# Load_Tester.net
KiCad netlist of a schematic drawn in Altium Designer
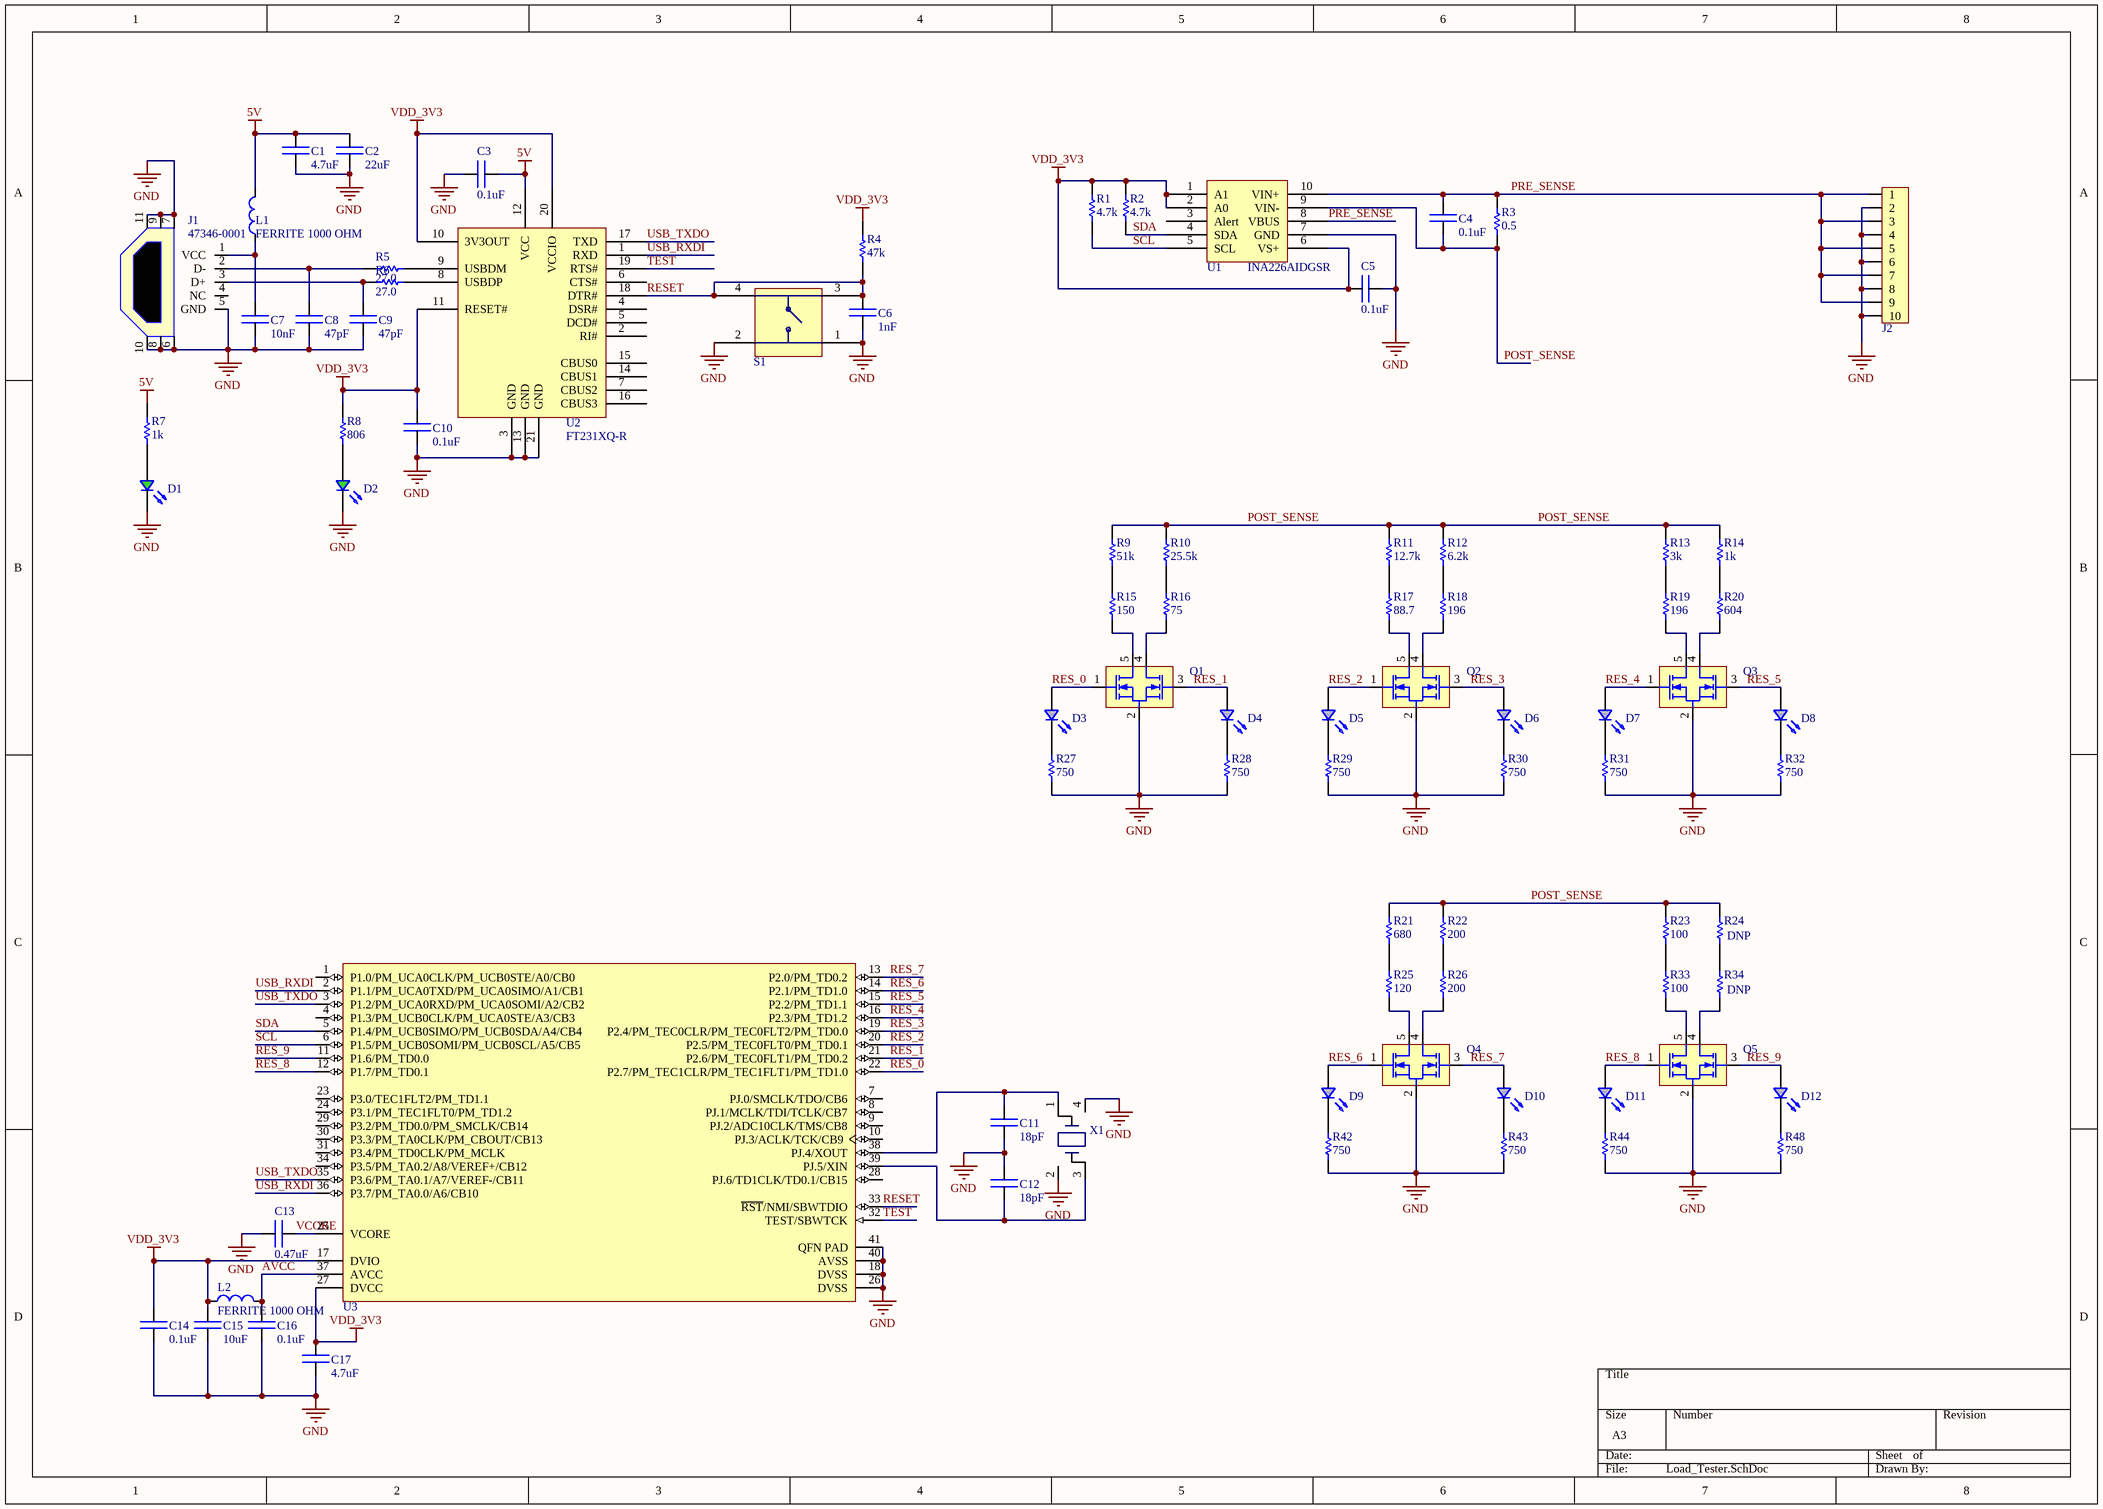
[diagram p0: Load_Tester.SchDoc]

(export (version "E")
  (design (tool "Eeschema 10.0.6"))
  (components
    (comp (ref "C1")
      (value "4.7uF")
      (footprint "0603_Cap_Generic")
      (description "CAP CER 4.7UF 35V X5R 0603")
      (fields
        (field (name "MC10 PART NUMBER") "100-00191")
        (field (name "MANUFACTURER") "TDK")
        (field (name "DRAWN BY") "EH")
      )
      (libsource (lib "MC10_Component_dblib_v1_0b2") (part "CAP CER 4.7UF 35V X5R 0603"))
    )
    (comp (ref "C2")
      (value "22uF")
      (footprint "0603_Cap_Generic")
      (description "CAP CER 22UF 10V X5R 0603")
      (fields
        (field (name "MC10 PART NUMBER") "100-00205")
        (field (name "MANUFACTURER") "TDK")
        (field (name "DRAWN BY") "EH")
      )
      (libsource (lib "MC10_Component_dblib_v1_0b2") (part "CAP CER 22UF 10V X5R 0603"))
    )
    (comp (ref "C3")
      (value "0.1uF")
      (footprint "0402_CAP_Generic")
      (description "CAP CER 0.1UF 25V X7R 0402")
      (fields
        (field (name "MC10 PART NUMBER") "100-00212")
        (field (name "MANUFACTURER") "TDK")
        (field (name "DRAWN BY") "EH")
      )
      (libsource (lib "MC10_Component_dblib_v1_0b2") (part "CAP CER 0.1UF 25V X7R 0402"))
    )
    (comp (ref "C4")
      (value "0.1uF")
      (footprint "0603_Cap_Generic")
      (description "CAP CER 0.1UF 25V X7R 0603")
      (fields
        (field (name "MC10 PART NUMBER") "100-00193")
        (field (name "MANUFACTURER") "TDK")
        (field (name "DRAWN BY") "EH")
      )
      (libsource (lib "MC10_Component_dblib_v1_0b2") (part "CAP CER 0.1UF 25V X7R 0603"))
    )
    (comp (ref "C5")
      (value "0.1uF")
      (footprint "0402_CAP_Generic")
      (description "CAP CER 0.1UF 25V X7R 0402")
      (fields
        (field (name "MC10 PART NUMBER") "100-00212")
        (field (name "MANUFACTURER") "TDK")
        (field (name "DRAWN BY") "EH")
      )
      (libsource (lib "MC10_Component_dblib_v1_0b2") (part "CAP CER 0.1UF 25V X7R 0402"))
    )
    (comp (ref "C6")
      (value "1nF")
      (footprint "0603_Cap_Generic")
      (description "CAP CER 1000PF 50V X7R 0603")
      (fields
        (field (name "MC10 PART NUMBER") "100-00211")
        (field (name "MANUFACTURER") "TDK")
        (field (name "DRAWN BY") "EH")
      )
      (libsource (lib "MC10_Component_dblib_v1_0b2") (part "CAP CER 1000PF 50V X7R 0603"))
    )
    (comp (ref "C7")
      (value "10nF")
      (footprint "0603_Cap_Generic")
      (description "CAP CER 10000PF 50V X7R 0603")
      (fields
        (field (name "MC10 PART NUMBER") "100-00189")
        (field (name "MANUFACTURER") "TDK")
        (field (name "DRAWN BY") "EH")
      )
      (libsource (lib "MC10_Component_dblib_v1_0b2") (part "CAP CER 10000PF 50V X7R 0603"))
    )
    (comp (ref "C8")
      (value "47pF")
      (footprint "0603_Cap_Generic")
      (description "CAP CER 47PF 50V C0G 0603")
      (fields
        (field (name "MC10 PART NUMBER") "100-00190")
        (field (name "MANUFACTURER") "TDK")
        (field (name "DRAWN BY") "EH")
      )
      (libsource (lib "MC10_Component_dblib_v1_0b2") (part "CAP CER 47PF 50V C0G 0603"))
    )
    (comp (ref "C9")
      (value "47pF")
      (footprint "0603_Cap_Generic")
      (description "CAP CER 47PF 50V C0G 0603")
      (fields
        (field (name "MC10 PART NUMBER") "100-00190")
        (field (name "MANUFACTURER") "TDK")
        (field (name "DRAWN BY") "EH")
      )
      (libsource (lib "MC10_Component_dblib_v1_0b2") (part "CAP CER 47PF 50V C0G 0603"))
    )
    (comp (ref "C10")
      (value "0.1uF")
      (footprint "0402_CAP_Generic")
      (description "CAP CER 0.1UF 25V X7R 0402")
      (fields
        (field (name "MC10 PART NUMBER") "100-00212")
        (field (name "MANUFACTURER") "TDK")
        (field (name "DRAWN BY") "EH")
      )
      (libsource (lib "MC10_Component_dblib_v1_0b2") (part "CAP CER 0.1UF 25V X7R 0402"))
    )
    (comp (ref "C11")
      (value "18pF")
      (footprint "0603_Cap_Generic")
      (description "CAP CER 18PF 50V C0G 0603")
      (fields
        (field (name "MC10 PART NUMBER") "100-00209")
        (field (name "MANUFACTURER") "TDK")
        (field (name "DRAWN BY") "EH")
      )
      (libsource (lib "MC10_Component_dblib_v1_0b2") (part "CAP CER 18PF 50V C0G 0603"))
    )
    (comp (ref "C12")
      (value "18pF")
      (footprint "0603_Cap_Generic")
      (description "CAP CER 18PF 50V C0G 0603")
      (fields
        (field (name "MC10 PART NUMBER") "100-00209")
        (field (name "MANUFACTURER") "TDK")
        (field (name "DRAWN BY") "EH")
      )
      (libsource (lib "MC10_Component_dblib_v1_0b2") (part "CAP CER 18PF 50V C0G 0603"))
    )
    (comp (ref "C13")
      (value "0.47uF")
      (footprint "0402_CAP_Generic")
      (description "CAP CER 0.47UF 10V X5R 0402")
      (fields
        (field (name "MC10 PART NUMBER") "100-00214")
        (field (name "MANUFACTURER") "TDK")
        (field (name "DRAWN BY") "EH")
      )
      (libsource (lib "MC10_Component_dblib_v1_0b2") (part "CAP CER 0.47UF 10V X5R 0402"))
    )
    (comp (ref "C14")
      (value "0.1uF")
      (footprint "0402_CAP_Generic")
      (description "CAP CER 0.1UF 25V X7R 0402")
      (fields
        (field (name "MC10 PART NUMBER") "100-00212")
        (field (name "MANUFACTURER") "TDK")
        (field (name "DRAWN BY") "EH")
      )
      (libsource (lib "MC10_Component_dblib_v1_0b2") (part "CAP CER 0.1UF 25V X7R 0402"))
    )
    (comp (ref "C15")
      (value "10uF")
      (footprint "0603_Cap_Generic")
      (description "CAP CER 10UF 10V JB 0603")
      (fields
        (field (name "MC10 PART NUMBER") "100-00208")
        (field (name "MANUFACTURER") "TDK")
        (field (name "DRAWN BY") "EH")
      )
      (libsource (lib "MC10_Component_dblib_v1_0b2") (part "CAP CER 10UF 10V JB 0603"))
    )
    (comp (ref "C16")
      (value "0.1uF")
      (footprint "0402_CAP_Generic")
      (description "CAP CER 0.1UF 25V X7R 0402")
      (fields
        (field (name "MC10 PART NUMBER") "100-00212")
        (field (name "MANUFACTURER") "TDK")
        (field (name "DRAWN BY") "EH")
      )
      (libsource (lib "MC10_Component_dblib_v1_0b2") (part "CAP CER 0.1UF 25V X7R 0402"))
    )
    (comp (ref "C17")
      (value "4.7uF")
      (footprint "0402_CAP_Generic")
      (description "CAP CER 4.7UF 10V X5R 0402")
      (fields
        (field (name "MC10 PART NUMBER") "100-00213")
        (field (name "MANUFACTURER") "TDK")
        (field (name "DRAWN BY") "EH")
      )
      (libsource (lib "MC10_Component_dblib_v1_0b2") (part "CAP CER 4.7UF 10V X5R 0402"))
    )
    (comp (ref "D1")
      (value "LED SMARTLED GREEN 570NM 0603")
      (footprint "0603_LED_with_mark")
      (fields
        (field (name "MANUFACTURER") "OSRAM Opto Semiconductors")
        (field (name "MANUFACTURER PART NUMBER") "LG L29K-G2J1-24-Z")
        (field (name "MC10 PART NUMBER") "200-00073")
        (field (name "DRAWN BY") "BLM")
      )
      (libsource (lib "MC10_Component_dblib_v1_0b2") (part "LED SMARTLED GREEN 570NM 0603"))
    )
    (comp (ref "D2")
      (value "LED SMARTLED GREEN 570NM 0603")
      (footprint "0603_LED_with_mark")
      (fields
        (field (name "MANUFACTURER") "OSRAM Opto Semiconductors")
        (field (name "MANUFACTURER PART NUMBER") "LG L29K-G2J1-24-Z")
        (field (name "MC10 PART NUMBER") "200-00073")
        (field (name "DRAWN BY") "BLM")
      )
      (libsource (lib "MC10_Component_dblib_v1_0b2") (part "LED SMARTLED GREEN 570NM 0603"))
    )
    (comp (ref "D3")
      (value "LED SMARTLED RED 630NM 0603 SMD")
      (footprint "0603_Diode-LED_Generic")
      (fields
        (field (name "MANUFACTURER") "OSRAM Opto Semiconductors")
        (field (name "MANUFACTURER PART NUMBER") "LS L29K-H1J2-1-Z")
        (field (name "MC10 PART NUMBER") "200-00031")
        (field (name "DRAWN BY") "BLM")
      )
      (libsource (lib "MC10_Component_dblib_v1_0b2") (part "LED SMARTLED RED 630NM 0603 SMD"))
    )
    (comp (ref "D4")
      (value "LED SMARTLED RED 630NM 0603 SMD")
      (footprint "0603_Diode-LED_Generic")
      (fields
        (field (name "MANUFACTURER") "OSRAM Opto Semiconductors")
        (field (name "MANUFACTURER PART NUMBER") "LS L29K-H1J2-1-Z")
        (field (name "MC10 PART NUMBER") "200-00031")
        (field (name "DRAWN BY") "BLM")
      )
      (libsource (lib "MC10_Component_dblib_v1_0b2") (part "LED SMARTLED RED 630NM 0603 SMD"))
    )
    (comp (ref "D5")
      (value "LED SMARTLED RED 630NM 0603 SMD")
      (footprint "0603_Diode-LED_Generic")
      (fields
        (field (name "MANUFACTURER") "OSRAM Opto Semiconductors")
        (field (name "MANUFACTURER PART NUMBER") "LS L29K-H1J2-1-Z")
        (field (name "MC10 PART NUMBER") "200-00031")
        (field (name "DRAWN BY") "BLM")
      )
      (libsource (lib "MC10_Component_dblib_v1_0b2") (part "LED SMARTLED RED 630NM 0603 SMD"))
    )
    (comp (ref "D6")
      (value "LED SMARTLED RED 630NM 0603 SMD")
      (footprint "0603_Diode-LED_Generic")
      (fields
        (field (name "MANUFACTURER") "OSRAM Opto Semiconductors")
        (field (name "MANUFACTURER PART NUMBER") "LS L29K-H1J2-1-Z")
        (field (name "MC10 PART NUMBER") "200-00031")
        (field (name "DRAWN BY") "BLM")
      )
      (libsource (lib "MC10_Component_dblib_v1_0b2") (part "LED SMARTLED RED 630NM 0603 SMD"))
    )
    (comp (ref "D7")
      (value "LED SMARTLED RED 630NM 0603 SMD")
      (footprint "0603_Diode-LED_Generic")
      (fields
        (field (name "MANUFACTURER") "OSRAM Opto Semiconductors")
        (field (name "MANUFACTURER PART NUMBER") "LS L29K-H1J2-1-Z")
        (field (name "MC10 PART NUMBER") "200-00031")
        (field (name "DRAWN BY") "BLM")
      )
      (libsource (lib "MC10_Component_dblib_v1_0b2") (part "LED SMARTLED RED 630NM 0603 SMD"))
    )
    (comp (ref "D8")
      (value "LED SMARTLED RED 630NM 0603 SMD")
      (footprint "0603_Diode-LED_Generic")
      (fields
        (field (name "MANUFACTURER") "OSRAM Opto Semiconductors")
        (field (name "MANUFACTURER PART NUMBER") "LS L29K-H1J2-1-Z")
        (field (name "MC10 PART NUMBER") "200-00031")
        (field (name "DRAWN BY") "BLM")
      )
      (libsource (lib "MC10_Component_dblib_v1_0b2") (part "LED SMARTLED RED 630NM 0603 SMD"))
    )
    (comp (ref "D9")
      (value "LED SMARTLED RED 630NM 0603 SMD")
      (footprint "0603_Diode-LED_Generic")
      (fields
        (field (name "MANUFACTURER") "OSRAM Opto Semiconductors")
        (field (name "MANUFACTURER PART NUMBER") "LS L29K-H1J2-1-Z")
        (field (name "MC10 PART NUMBER") "200-00031")
        (field (name "DRAWN BY") "BLM")
      )
      (libsource (lib "MC10_Component_dblib_v1_0b2") (part "LED SMARTLED RED 630NM 0603 SMD"))
    )
    (comp (ref "D10")
      (value "LED SMARTLED RED 630NM 0603 SMD")
      (footprint "0603_Diode-LED_Generic")
      (fields
        (field (name "MANUFACTURER") "OSRAM Opto Semiconductors")
        (field (name "MANUFACTURER PART NUMBER") "LS L29K-H1J2-1-Z")
        (field (name "MC10 PART NUMBER") "200-00031")
        (field (name "DRAWN BY") "BLM")
      )
      (libsource (lib "MC10_Component_dblib_v1_0b2") (part "LED SMARTLED RED 630NM 0603 SMD"))
    )
    (comp (ref "D11")
      (value "LED SMARTLED RED 630NM 0603 SMD")
      (footprint "0603_Diode-LED_Generic")
      (fields
        (field (name "MANUFACTURER") "OSRAM Opto Semiconductors")
        (field (name "MANUFACTURER PART NUMBER") "LS L29K-H1J2-1-Z")
        (field (name "MC10 PART NUMBER") "200-00031")
        (field (name "DRAWN BY") "BLM")
      )
      (libsource (lib "MC10_Component_dblib_v1_0b2") (part "LED SMARTLED RED 630NM 0603 SMD"))
    )
    (comp (ref "D12")
      (value "LED SMARTLED RED 630NM 0603 SMD")
      (footprint "0603_Diode-LED_Generic")
      (fields
        (field (name "MANUFACTURER") "OSRAM Opto Semiconductors")
        (field (name "MANUFACTURER PART NUMBER") "LS L29K-H1J2-1-Z")
        (field (name "MC10 PART NUMBER") "200-00031")
        (field (name "DRAWN BY") "BLM")
      )
      (libsource (lib "MC10_Component_dblib_v1_0b2") (part "LED SMARTLED RED 630NM 0603 SMD"))
    )
    (comp (ref "J1")
      (value "USB_MICRO-SMT-F_47346-0001")
      (footprint "USB_MICRO_SD-47346-001")
      (description "CONNECTOR MICRO USB B RECPT BTTM MOUNT ASSY")
      (fields
        (field (name "MANUFACTURER") "Molex")
        (field (name "MANUFACTURER PART NUMBER") "47346-0001")
        (field (name "MC10 PART NUMBER") "120-00050")
        (field (name "DRAWN BY") "BKM")
      )
      (libsource (lib "MC10_Component_dblib_v1_0b2") (part "USB_MICRO-SMT-F_47346-0001"))
    )
    (comp (ref "J2")
      (value "IDC BOX HEADER 0.050 10 POS")
      (footprint "IDC BOX HEADER 0.050 10 POS")
      (fields
        (field (name "MANUFACTURER") "CNC Tech")
        (field (name "MANUFACTURER PART NUMBER") "3220-10-0300-00")
        (field (name "MC10 PART NUMBER") "120-00125")
        (field (name "DRAWN BY") "EH")
      )
      (libsource (lib "MC10_Component_dblib_v1_0b2") (part "IDC BOX HEADER 0.050 10 POS"))
    )
    (comp (ref "L1")
      (value "FERRITE 1000 OHM")
      (footprint "FERRITE CHIP 1000 OHM 300MA 0402")
      (description "FERRITE CHIP 1000 OHM 300MA 0402")
      (fields
        (field (name "MANUFACTURER") "Samsung")
        (field (name "MANUFACTURER PART NUMBER") "CIM05U102NC")
        (field (name "DRAWN BY") "AC")
      )
      (libsource (lib "MC10_Component_dblib_v1_0b2") (part "FERRITE CHIP 1000 OHM 300MA 0402"))
    )
    (comp (ref "L2")
      (value "FERRITE 1000 OHM")
      (footprint "FERRITE CHIP 1000 OHM 300MA 0402")
      (description "FERRITE CHIP 1000 OHM 300MA 0402")
      (fields
        (field (name "MANUFACTURER") "Samsung")
        (field (name "MANUFACTURER PART NUMBER") "CIM05U102NC")
        (field (name "DRAWN BY") "AC")
      )
      (libsource (lib "") (part "FERRITE CHIP 1000 OHM 300MA 0402_1"))
    )
    (comp (ref "Q1")
      (value "MOSFET 2N-CH 30V 2A TSMT5")
      (footprint "SOT23-5 Generic Package")
      (fields
        (field (name "MANUFACTURER") "Rohm Semiconductor")
        (field (name "MANUFACTURER PART NUMBER") "QS5K2TR")
        (field (name "MC10 PART NUMBER") "200-00118")
        (field (name "DRAWN BY") "EH")
      )
      (libsource (lib "MC10_Component_dblib_v1_0b2") (part "MOSFET 2N-CH 30V 2A TSMT5"))
    )
    (comp (ref "Q2")
      (value "MOSFET 2N-CH 30V 2A TSMT5")
      (footprint "SOT23-5 Generic Package")
      (fields
        (field (name "MANUFACTURER") "Rohm Semiconductor")
        (field (name "MANUFACTURER PART NUMBER") "QS5K2TR")
        (field (name "MC10 PART NUMBER") "200-00118")
        (field (name "DRAWN BY") "EH")
      )
      (libsource (lib "MC10_Component_dblib_v1_0b2") (part "MOSFET 2N-CH 30V 2A TSMT5"))
    )
    (comp (ref "Q3")
      (value "MOSFET 2N-CH 30V 2A TSMT5")
      (footprint "SOT23-5 Generic Package")
      (fields
        (field (name "MANUFACTURER") "Rohm Semiconductor")
        (field (name "MANUFACTURER PART NUMBER") "QS5K2TR")
        (field (name "MC10 PART NUMBER") "200-00118")
        (field (name "DRAWN BY") "EH")
      )
      (libsource (lib "MC10_Component_dblib_v1_0b2") (part "MOSFET 2N-CH 30V 2A TSMT5"))
    )
    (comp (ref "Q4")
      (value "MOSFET 2N-CH 30V 2A TSMT5")
      (footprint "SOT23-5 Generic Package")
      (fields
        (field (name "MANUFACTURER") "Rohm Semiconductor")
        (field (name "MANUFACTURER PART NUMBER") "QS5K2TR")
        (field (name "MC10 PART NUMBER") "200-00118")
        (field (name "DRAWN BY") "EH")
      )
      (libsource (lib "MC10_Component_dblib_v1_0b2") (part "MOSFET 2N-CH 30V 2A TSMT5"))
    )
    (comp (ref "Q5")
      (value "MOSFET 2N-CH 30V 2A TSMT5")
      (footprint "SOT23-5 Generic Package")
      (fields
        (field (name "MANUFACTURER") "Rohm Semiconductor")
        (field (name "MANUFACTURER PART NUMBER") "QS5K2TR")
        (field (name "MC10 PART NUMBER") "200-00118")
        (field (name "DRAWN BY") "EH")
      )
      (libsource (lib "MC10_Component_dblib_v1_0b2") (part "MOSFET 2N-CH 30V 2A TSMT5"))
    )
    (comp (ref "R1")
      (value "4.7k")
      (footprint "0402_Res_Generic")
      (description "RES SMD 4.7K OHM 1% 1/10W 0402")
      (fields
        (field (name "MANUFACTURER") "Panasonic")
        (field (name "MANUFACTURER PART NUMBER") "ERJ-2RKF4701X")
        (field (name "DRAWN BY") "EH")
      )
      (libsource (lib "MC10_Component_dblib_v1_0b2") (part "RES SMD 4.7K OHM 1% 1/10W 0402"))
    )
    (comp (ref "R2")
      (value "4.7k")
      (footprint "0402_Res_Generic")
      (description "RES SMD 4.7K OHM 1% 1/10W 0402")
      (fields
        (field (name "MANUFACTURER") "Panasonic")
        (field (name "MANUFACTURER PART NUMBER") "ERJ-2RKF4701X")
        (field (name "DRAWN BY") "EH")
      )
      (libsource (lib "MC10_Component_dblib_v1_0b2") (part "RES SMD 4.7K OHM 1% 1/10W 0402"))
    )
    (comp (ref "R3")
      (value "0.5")
      (footprint "0603_Res_Generic")
      (description "RES SMD 0.5 OHM 1% 1/8W 0603")
      (fields
        (field (name "MANUFACTURER") "Stackpole Electronics")
        (field (name "MANUFACTURER PART NUMBER") "CSR0603FKR500")
        (field (name "DRAWN BY") "EH")
      )
      (libsource (lib "MC10_Component_dblib_v1_0b2") (part "RES SMD 0.5 OHM 1% 1/8W 0603"))
    )
    (comp (ref "R4")
      (value "47k")
      (footprint "0603_Res_Generic")
      (description "RES SMD 47K OHM 1% 1/10W 0603")
      (fields
        (field (name "MANUFACTURER") "Panasonic")
        (field (name "MANUFACTURER PART NUMBER") "ERJ-3EKF4702V")
        (field (name "DRAWN BY") "EH")
      )
      (libsource (lib "MC10_Component_dblib_v1_0b2") (part "RES SMD 47K OHM 1% 1/10W 0603"))
    )
    (comp (ref "R5")
      (value "27.0")
      (footprint "0603_Res_Generic")
      (description "RES SMD 27 OHM 1% 1/10W 0603")
      (fields
        (field (name "MANUFACTURER") "Panasonic")
        (field (name "MANUFACTURER PART NUMBER") "ERJ-3EKF27R0V")
        (field (name "DRAWN BY") "EH")
      )
      (libsource (lib "MC10_Component_dblib_v1_0b2") (part "RES SMD 27 OHM 1% 1/10W 0603"))
    )
    (comp (ref "R6")
      (value "27.0")
      (footprint "0603_Res_Generic")
      (description "RES SMD 27 OHM 1% 1/10W 0603")
      (fields
        (field (name "MANUFACTURER") "Panasonic")
        (field (name "MANUFACTURER PART NUMBER") "ERJ-3EKF27R0V")
        (field (name "DRAWN BY") "EH")
      )
      (libsource (lib "MC10_Component_dblib_v1_0b2") (part "RES SMD 27 OHM 1% 1/10W 0603"))
    )
    (comp (ref "R7")
      (value "1k")
      (footprint "0603_Res_Generic")
      (description "RES SMD 1K OHM 5% 1/10W 0603")
      (fields
        (field (name "PART NUMBER") "RES SMD 1K OHM 5% 1/10W 0603 (2)")
        (field (name "MANUFACTURER") "Panasonic")
        (field (name "DRAWN BY") "EH")
      )
      (libsource (lib "MC10_Component_dblib_v1_0b2") (part "RES SMD 1K OHM 5% 1/10W 0603 (2)"))
    )
    (comp (ref "R8")
      (value "806")
      (footprint "0603_Res_Generic")
      (description "RES SMD 806 OHM 1% 1/10W 0603")
      (fields
        (field (name "MANUFACTURER") "Panasonic")
        (field (name "MANUFACTURER PART NUMBER") "ERJ-3EKF8060V")
        (field (name "DRAWN BY") "EH")
      )
      (libsource (lib "MC10_Component_dblib_v1_0b2") (part "RES SMD 806 OHM 1% 1/10W 0603"))
    )
    (comp (ref "R9")
      (value "51k")
      (footprint "0805_Res_Generic")
      (description "RES SMD 51K OHM 1% 1/8W 0805")
      (fields
        (field (name "MANUFACTURER") "Panasonic")
        (field (name "MANUFACTURER PART NUMBER") "ERJ-6ENF5102V")
        (field (name "DRAWN BY") "EH")
      )
      (libsource (lib "MC10_Component_dblib_v1_0b2") (part "RES SMD 51K OHM 1% 1/8W 0805"))
    )
    (comp (ref "R10")
      (value "25.5k")
      (footprint "0805_Res_Generic")
      (description "RES SMD 25.5K OHM 1% 1/8W 0805")
      (fields
        (field (name "MANUFACTURER") "Panasonic")
        (field (name "MANUFACTURER PART NUMBER") "ERJ-6ENF2552V")
        (field (name "DRAWN BY") "EH")
      )
      (libsource (lib "MC10_Component_dblib_v1_0b2") (part "RES SMD 25.5K OHM 1% 1/8W 0805"))
    )
    (comp (ref "R11")
      (value "12.7k")
      (footprint "0805_Res_Generic")
      (description "RES SMD 12.7K OHM 1% 1/8W 0805")
      (fields
        (field (name "MANUFACTURER") "Panasonic")
        (field (name "MANUFACTURER PART NUMBER") "ERJ-6ENF1272V")
        (field (name "DRAWN BY") "EH")
      )
      (libsource (lib "MC10_Component_dblib_v1_0b2") (part "RES SMD 12.7K OHM 1% 1/8W 0805"))
    )
    (comp (ref "R12")
      (value "6.2k")
      (footprint "0805_Res_Generic")
      (description "RES SMD 6.2K OHM 1% 1/8W 0805")
      (fields
        (field (name "MANUFACTURER") "Panasonic")
        (field (name "MANUFACTURER PART NUMBER") "ERJ-6ENF6201V")
        (field (name "DRAWN BY") "EH")
      )
      (libsource (lib "MC10_Component_dblib_v1_0b2") (part "RES SMD 6.2K OHM 1% 1/8W 0805"))
    )
    (comp (ref "R13")
      (value "3k")
      (footprint "0805_Res_Generic")
      (description "RES SMD 3K OHM 1% 1/8W 0805")
      (fields
        (field (name "MANUFACTURER") "Panasonic")
        (field (name "MANUFACTURER PART NUMBER") "ERJ-6ENF3001V")
        (field (name "DRAWN BY") "EH")
      )
      (libsource (lib "MC10_Component_dblib_v1_0b2") (part "RES SMD 3K OHM 1% 1/8W 0805"))
    )
    (comp (ref "R14")
      (value "1k")
      (footprint "0805_Res_Generic")
      (description "RES SMD 1K OHM 1% 1/8W 0805")
      (fields
        (field (name "MANUFACTURER") "Panasonic")
        (field (name "MANUFACTURER PART NUMBER") "ERJ-6ENF1001V")
        (field (name "DRAWN BY") "EH")
      )
      (libsource (lib "MC10_Component_dblib_v1_0b2") (part "RES SMD 1K OHM 1% 1/8W 0805"))
    )
    (comp (ref "R15")
      (value "150")
      (footprint "0805_Res_Generic")
      (description "RES SMD 150 OHM 1% 1/8W 0805")
      (fields
        (field (name "MANUFACTURER") "Panasonic")
        (field (name "MANUFACTURER PART NUMBER") "ERJ-6ENF1500V")
        (field (name "DRAWN BY") "EH")
      )
      (libsource (lib "MC10_Component_dblib_v1_0b2") (part "RES SMD 150 OHM 1% 1/8W 0805"))
    )
    (comp (ref "R16")
      (value "75")
      (footprint "0805_Res_Generic")
      (description "RES SMD 75 OHM 1% 1/8W 0805")
      (fields
        (field (name "MANUFACTURER") "Panasonic")
        (field (name "MANUFACTURER PART NUMBER") "ERJ-6ENF75R0V")
        (field (name "DRAWN BY") "EH")
      )
      (libsource (lib "MC10_Component_dblib_v1_0b2") (part "RES SMD 75 OHM 1% 1/8W 0805"))
    )
    (comp (ref "R17")
      (value "88.7")
      (footprint "0805_Res_Generic")
      (description "RES SMD 88.7 OHM 1% 1/8W 0805")
      (fields
        (field (name "MANUFACTURER") "Panasonic")
        (field (name "MANUFACTURER PART NUMBER") "ERJ-6ENF88R7V")
        (field (name "DRAWN BY") "EH")
      )
      (libsource (lib "MC10_Component_dblib_v1_0b2") (part "RES SMD 88.7 OHM 1% 1/8W 0805"))
    )
    (comp (ref "R18")
      (value "196")
      (footprint "0805_Res_Generic")
      (description "RES SMD 196 OHM 1% 1/8W 0805")
      (fields
        (field (name "MANUFACTURER") "Panasonic")
        (field (name "MANUFACTURER PART NUMBER") "ERJ-6ENF1960V")
        (field (name "DRAWN BY") "EH")
      )
      (libsource (lib "MC10_Component_dblib_v1_0b2") (part "RES SMD 196 OHM 1% 1/8W 0805"))
    )
    (comp (ref "R19")
      (value "196")
      (footprint "0805_Res_Generic")
      (description "RES SMD 196 OHM 1% 1/8W 0805")
      (fields
        (field (name "MANUFACTURER") "Panasonic")
        (field (name "MANUFACTURER PART NUMBER") "ERJ-6ENF1960V")
        (field (name "DRAWN BY") "EH")
      )
      (libsource (lib "MC10_Component_dblib_v1_0b2") (part "RES SMD 196 OHM 1% 1/8W 0805"))
    )
    (comp (ref "R20")
      (value "604")
      (footprint "0805_Res_Generic")
      (description "RES SMD 604 OHM 1% 1/8W 0805")
      (fields
        (field (name "MANUFACTURER") "Panasonic")
        (field (name "MANUFACTURER PART NUMBER") "ERJ-6ENF6040V")
        (field (name "DRAWN BY") "EH")
      )
      (libsource (lib "MC10_Component_dblib_v1_0b2") (part "RES SMD 604 OHM 1% 1/8W 0805"))
    )
    (comp (ref "R21")
      (value "680")
      (footprint "0805_Res_Generic")
      (description "RES SMD 680 OHM 1% 1/2W 0805")
      (fields
        (field (name "MANUFACTURER") "Panasonic")
        (field (name "MANUFACTURER PART NUMBER") "ERJ-P6WF6800V")
        (field (name "DRAWN BY") "EH")
      )
      (libsource (lib "MC10_Component_dblib_v1_0b2") (part "RES SMD 680 OHM 1% 1/2W 0805"))
    )
    (comp (ref "R22")
      (value "200")
      (footprint "0805_Res_Generic")
      (description "RES SMD 200 OHM 1% 1/2W 0805")
      (fields
        (field (name "MANUFACTURER") "Panasonic")
        (field (name "MANUFACTURER PART NUMBER") "ERJ-P06F2000V")
        (field (name "DRAWN BY") "EH")
      )
      (libsource (lib "MC10_Component_dblib_v1_0b2") (part "RES SMD 200 OHM 1% 1/2W 0805"))
    )
    (comp (ref "R23")
      (value "100")
      (footprint "0805_Res_Generic")
      (description "RES SMD 100 OHM 0.1% 5/8W 0805")
      (fields
        (field (name "MANUFACTURER") "Vishay")
        (field (name "MANUFACTURER PART NUMBER") "PHP00805E1000BST1")
        (field (name "DRAWN BY") "EH")
      )
      (libsource (lib "MC10_Component_dblib_v1_0b2") (part "RES SMD 100 OHM 0.1% 5/8W 0805"))
    )
    (comp (ref "R24")
      (value "DNP")
      (footprint "0805_Res_Generic")
      (fields
        (field (name "PART NUMBER") "RES SMD 0.0 OHM JUMPER 1/8W 0805")
        (field (name "MANUFACTURER") "Panasonic")
        (field (name "MANUFACTURER PART NUMBER") "ERJ-6GEY0R00V")
        (field (name "DRAWN BY") "EH")
      )
      (libsource (lib "MC10_Component_dblib_v1_0b2") (part "RES SMD 0.0 OHM JUMPER 1/8W 0805"))
    )
    (comp (ref "R25")
      (value "120")
      (footprint "0805_Res_Generic")
      (description "RES SMD 120 OHM 1% 1/2W 0805")
      (fields
        (field (name "MANUFACTURER") "Panasonic")
        (field (name "MANUFACTURER PART NUMBER") "ERJ-P6WF1200V")
        (field (name "DRAWN BY") "EH")
      )
      (libsource (lib "MC10_Component_dblib_v1_0b2") (part "RES SMD 120 OHM 1% 1/2W 0805"))
    )
    (comp (ref "R26")
      (value "200")
      (footprint "0805_Res_Generic")
      (description "RES SMD 200 OHM 1% 1/2W 0805")
      (fields
        (field (name "MANUFACTURER") "Panasonic")
        (field (name "MANUFACTURER PART NUMBER") "ERJ-P06F2000V")
        (field (name "DRAWN BY") "EH")
      )
      (libsource (lib "MC10_Component_dblib_v1_0b2") (part "RES SMD 200 OHM 1% 1/2W 0805"))
    )
    (comp (ref "R27")
      (value "750")
      (footprint "0603_Res_Generic")
      (description "RES SMD 750 OHM 1% 1/10W 0603")
      (fields
        (field (name "MANUFACTURER") "Panasonic")
        (field (name "MANUFACTURER PART NUMBER") "ERJ-3EKF7500V")
        (field (name "DRAWN BY") "EH")
      )
      (libsource (lib "MC10_Component_dblib_v1_0b2") (part "RES SMD 750 OHM 1% 1/10W 0603"))
    )
    (comp (ref "R28")
      (value "750")
      (footprint "0603_Res_Generic")
      (description "RES SMD 750 OHM 1% 1/10W 0603")
      (fields
        (field (name "MANUFACTURER") "Panasonic")
        (field (name "MANUFACTURER PART NUMBER") "ERJ-3EKF7500V")
        (field (name "DRAWN BY") "EH")
      )
      (libsource (lib "MC10_Component_dblib_v1_0b2") (part "RES SMD 750 OHM 1% 1/10W 0603"))
    )
    (comp (ref "R29")
      (value "750")
      (footprint "0603_Res_Generic")
      (description "RES SMD 750 OHM 1% 1/10W 0603")
      (fields
        (field (name "MANUFACTURER") "Panasonic")
        (field (name "MANUFACTURER PART NUMBER") "ERJ-3EKF7500V")
        (field (name "DRAWN BY") "EH")
      )
      (libsource (lib "MC10_Component_dblib_v1_0b2") (part "RES SMD 750 OHM 1% 1/10W 0603"))
    )
    (comp (ref "R30")
      (value "750")
      (footprint "0603_Res_Generic")
      (description "RES SMD 750 OHM 1% 1/10W 0603")
      (fields
        (field (name "MANUFACTURER") "Panasonic")
        (field (name "MANUFACTURER PART NUMBER") "ERJ-3EKF7500V")
        (field (name "DRAWN BY") "EH")
      )
      (libsource (lib "MC10_Component_dblib_v1_0b2") (part "RES SMD 750 OHM 1% 1/10W 0603"))
    )
    (comp (ref "R31")
      (value "750")
      (footprint "0603_Res_Generic")
      (description "RES SMD 750 OHM 1% 1/10W 0603")
      (fields
        (field (name "MANUFACTURER") "Panasonic")
        (field (name "MANUFACTURER PART NUMBER") "ERJ-3EKF7500V")
        (field (name "DRAWN BY") "EH")
      )
      (libsource (lib "MC10_Component_dblib_v1_0b2") (part "RES SMD 750 OHM 1% 1/10W 0603"))
    )
    (comp (ref "R32")
      (value "750")
      (footprint "0603_Res_Generic")
      (description "RES SMD 750 OHM 1% 1/10W 0603")
      (fields
        (field (name "MANUFACTURER") "Panasonic")
        (field (name "MANUFACTURER PART NUMBER") "ERJ-3EKF7500V")
        (field (name "DRAWN BY") "EH")
      )
      (libsource (lib "MC10_Component_dblib_v1_0b2") (part "RES SMD 750 OHM 1% 1/10W 0603"))
    )
    (comp (ref "R33")
      (value "100")
      (footprint "0805_Res_Generic")
      (description "RES SMD 100 OHM 0.1% 5/8W 0805")
      (fields
        (field (name "MANUFACTURER") "Vishay")
        (field (name "MANUFACTURER PART NUMBER") "PHP00805E1000BST1")
        (field (name "DRAWN BY") "EH")
      )
      (libsource (lib "MC10_Component_dblib_v1_0b2") (part "RES SMD 100 OHM 0.1% 5/8W 0805"))
    )
    (comp (ref "R34")
      (value "DNP")
      (footprint "0805_Res_Generic")
      (fields
        (field (name "PART NUMBER") "RES SMD 0.0 OHM JUMPER 1/8W 0805")
        (field (name "MANUFACTURER") "Panasonic")
        (field (name "MANUFACTURER PART NUMBER") "ERJ-6GEY0R00V")
        (field (name "DRAWN BY") "EH")
      )
      (libsource (lib "MC10_Component_dblib_v1_0b2") (part "RES SMD 0.0 OHM JUMPER 1/8W 0805"))
    )
    (comp (ref "R42")
      (value "750")
      (footprint "0603_Res_Generic")
      (description "RES SMD 750 OHM 1% 1/10W 0603")
      (fields
        (field (name "MANUFACTURER") "Panasonic")
        (field (name "MANUFACTURER PART NUMBER") "ERJ-3EKF7500V")
        (field (name "DRAWN BY") "EH")
      )
      (libsource (lib "MC10_Component_dblib_v1_0b2") (part "RES SMD 750 OHM 1% 1/10W 0603"))
    )
    (comp (ref "R43")
      (value "750")
      (footprint "0603_Res_Generic")
      (description "RES SMD 750 OHM 1% 1/10W 0603")
      (fields
        (field (name "MANUFACTURER") "Panasonic")
        (field (name "MANUFACTURER PART NUMBER") "ERJ-3EKF7500V")
        (field (name "DRAWN BY") "EH")
      )
      (libsource (lib "MC10_Component_dblib_v1_0b2") (part "RES SMD 750 OHM 1% 1/10W 0603"))
    )
    (comp (ref "R44")
      (value "750")
      (footprint "0603_Res_Generic")
      (description "RES SMD 750 OHM 1% 1/10W 0603")
      (fields
        (field (name "MANUFACTURER") "Panasonic")
        (field (name "MANUFACTURER PART NUMBER") "ERJ-3EKF7500V")
        (field (name "DRAWN BY") "EH")
      )
      (libsource (lib "MC10_Component_dblib_v1_0b2") (part "RES SMD 750 OHM 1% 1/10W 0603"))
    )
    (comp (ref "R48")
      (value "750")
      (footprint "0603_Res_Generic")
      (description "RES SMD 750 OHM 1% 1/10W 0603")
      (fields
        (field (name "MANUFACTURER") "Panasonic")
        (field (name "MANUFACTURER PART NUMBER") "ERJ-3EKF7500V")
        (field (name "DRAWN BY") "EH")
      )
      (libsource (lib "MC10_Component_dblib_v1_0b2") (part "RES SMD 750 OHM 1% 1/10W 0603"))
    )
    (comp (ref "S1")
      (value "SWITCH TACTILE SPST-NO 0.05A 12V")
      (footprint "SWITCH TACTILE SPST-NO 0.05A 12V")
      (fields
        (field (name "MANUFACTURER") "C&K Components")
        (field (name "MANUFACTURER PART NUMBER") "PTS645SK50SMTR92 LFS")
        (field (name "MC10 PART NUMBER") "410-00022")
        (field (name "DRAWN BY") "BLM")
      )
      (libsource (lib "MC10_Component_dblib_v1_0b2") (part "SWITCH TACTILE SPST-NO 0.05A 12V"))
    )
    (comp (ref "U1")
      (value "INA226AIDGSR")
      (footprint "10-TFSOP")
      (description "IC MONITOR PWR/CURR BIDIR 10MSOP")
      (fields
        (field (name "MANUFACTURER") "Texas Instruments")
        (field (name "MC10 PART NUMBER") "202-00053")
        (field (name "DRAWN BY") "BLM")
      )
      (libsource (lib "MC10_Component_dblib_v1_0b2") (part "IC MONITOR PWR/CURR BIDIR 10MSOP"))
    )
    (comp (ref "U2")
      (value "FT231XQ-R")
      (footprint "IC USB SERIAL FULL UART 20QFN")
      (description "DNP")
      (fields
        (field (name "PART NUMBER") "IC USB SERIAL FULL UART 20QFN")
        (field (name "MANUFACTURER") "FTDI")
        (field (name "DRAWN BY") "BLM")
      )
      (libsource (lib "MC10_Component_dblib_v1_0b2") (part "IC USB SERIAL FULL UART 20QFN"))
    )
    (comp (ref "U3")
      (value "IC MCU 16BIT 8KB FLASH 40WQFN")
      (footprint "IC MCU 16BIT 8KB FLASH 40WQFN")
      (description "DNP")
      (fields
        (field (name "MANUFACTURER") "Texas Instruments")
        (field (name "MANUFACTURER PART NUMBER") "MSP430F5132IRSBR")
        (field (name "DRAWN BY") "BLM")
      )
      (libsource (lib "MC10_Component_dblib_v1_0b2") (part "IC MCU 16BIT 8KB FLASH 40WQFN"))
    )
    (comp (ref "X1")
      (value "CRYSTAL 13.56MHZ 10PF SMD")
      (footprint "CRYSTAL 13.56MHZ 10PF SMD")
      (fields
        (field (name "MANUFACTURER") "Abracon")
        (field (name "MANUFACTURER PART NUMBER") "ABM8G-13.560MHZ-4Y-T3")
        (field (name "MC10 PART NUMBER") "205-00012")
        (field (name "DRAWN BY") "BLM")
      )
      (libsource (lib "MC10_Component_dblib_v1_0b2") (part "CRYSTAL 13.56MHZ 10PF SMD"))
    )
  )
  (nets
    (net (code "1") (name "/AVCC") (class "Default")
      (node (ref "C16") (pin "1") (pintype "power_in"))
      (node (ref "L2") (pin "1") (pinfunction "1_1") (pintype "passive"))
      (node (ref "U3") (pin "37") (pinfunction "AVCC_37") (pintype "power_in"))
    )
    (net (code "2") (name "/POST_SENSE") (class "Default")
      (node (ref "C4") (pin "2") (pintype "power_in"))
      (node (ref "R10") (pin "2") (pinfunction "2_2") (pintype "passive"))
      (node (ref "R11") (pin "2") (pinfunction "2_2") (pintype "passive"))
      (node (ref "R12") (pin "2") (pinfunction "2_2") (pintype "passive"))
      (node (ref "R13") (pin "2") (pinfunction "2_2") (pintype "passive"))
      (node (ref "R14") (pin "2") (pinfunction "2_2") (pintype "passive"))
      (node (ref "R21") (pin "2") (pinfunction "2_2") (pintype "passive"))
      (node (ref "R22") (pin "2") (pinfunction "2_2") (pintype "passive"))
      (node (ref "R23") (pin "2") (pinfunction "2_2") (pintype "passive"))
      (node (ref "R24") (pin "2") (pinfunction "2_2") (pintype "passive"))
      (node (ref "R3") (pin "1") (pinfunction "1_1") (pintype "passive"))
      (node (ref "R9") (pin "2") (pinfunction "2_2") (pintype "passive"))
      (node (ref "U1") (pin "9") (pinfunction "VIN-_9") (pintype "passive"))
    )
    (net (code "3") (name "/PRE_SENSE") (class "Default")
      (node (ref "C4") (pin "1") (pintype "power_in"))
      (node (ref "J2") (pin "1") (pinfunction "1_1") (pintype "passive"))
      (node (ref "J2") (pin "3") (pinfunction "3_3") (pintype "passive"))
      (node (ref "J2") (pin "5") (pinfunction "5_5") (pintype "passive"))
      (node (ref "J2") (pin "7") (pinfunction "7_7") (pintype "passive"))
      (node (ref "J2") (pin "9") (pinfunction "9_9") (pintype "passive"))
      (node (ref "R3") (pin "2") (pinfunction "2_2") (pintype "passive"))
      (node (ref "U1") (pin "10") (pinfunction "VIN+_10") (pintype "passive"))
      (node (ref "U1") (pin "8") (pinfunction "VBUS_8") (pintype "passive"))
    )
    (net (code "4") (name "/RESET") (class "Default")
      (node (ref "C6") (pin "1") (pintype "power_in"))
      (node (ref "R4") (pin "1") (pinfunction "1_1") (pintype "passive"))
      (node (ref "S1") (pin "3") (pinfunction "3_3") (pintype "passive"))
      (node (ref "S1") (pin "4") (pinfunction "4_4") (pintype "passive"))
      (node (ref "U2") (pin "18") (pinfunction "DTR#_18") (pintype "passive"))
      (node (ref "U3") (pin "33") (pinfunction "~{RST}/NMI/SBWTDIO_33") (pintype "bidirectional"))
    )
    (net (code "5") (name "/RES_0") (class "Default")
      (node (ref "D3") (pin "A") (pinfunction "A_A") (pintype "passive"))
      (node (ref "Q1") (pin "1") (pinfunction "G1_1") (pintype "passive"))
      (node (ref "U3") (pin "22") (pinfunction "P2.7/PM_TEC1CLR/PM_TEC1FLT1/PM_TD1.0_22") (pintype "bidirectional"))
    )
    (net (code "6") (name "/RES_1") (class "Default")
      (node (ref "D4") (pin "A") (pinfunction "A_A") (pintype "passive"))
      (node (ref "Q1") (pin "3") (pinfunction "G2_3") (pintype "passive"))
      (node (ref "U3") (pin "21") (pinfunction "P2.6/PM_TEC0FLT1/PM_TD0.2_21") (pintype "bidirectional"))
    )
    (net (code "7") (name "/RES_2") (class "Default")
      (node (ref "D5") (pin "A") (pinfunction "A_A") (pintype "passive"))
      (node (ref "Q2") (pin "1") (pinfunction "G1_1") (pintype "passive"))
      (node (ref "U3") (pin "20") (pinfunction "P2.5/PM_TEC0FLT0/PM_TD0.1_20") (pintype "bidirectional"))
    )
    (net (code "8") (name "/RES_3") (class "Default")
      (node (ref "D6") (pin "A") (pinfunction "A_A") (pintype "passive"))
      (node (ref "Q2") (pin "3") (pinfunction "G2_3") (pintype "passive"))
      (node (ref "U3") (pin "19") (pinfunction "P2.4/PM_TEC0CLR/PM_TEC0FLT2/PM_TD0.0_19") (pintype "bidirectional"))
    )
    (net (code "9") (name "/RES_4") (class "Default")
      (node (ref "D7") (pin "A") (pinfunction "A_A") (pintype "passive"))
      (node (ref "Q3") (pin "1") (pinfunction "G1_1") (pintype "passive"))
      (node (ref "U3") (pin "16") (pinfunction "P2.3/PM_TD1.2_16") (pintype "bidirectional"))
    )
    (net (code "10") (name "/RES_5") (class "Default")
      (node (ref "D8") (pin "A") (pinfunction "A_A") (pintype "passive"))
      (node (ref "Q3") (pin "3") (pinfunction "G2_3") (pintype "passive"))
      (node (ref "U3") (pin "15") (pinfunction "P2.2/PM_TD1.1_15") (pintype "bidirectional"))
    )
    (net (code "11") (name "/RES_6") (class "Default")
      (node (ref "D9") (pin "A") (pinfunction "A_A") (pintype "passive"))
      (node (ref "Q4") (pin "1") (pinfunction "G1_1") (pintype "passive"))
      (node (ref "U3") (pin "14") (pinfunction "P2.1/PM_TD1.0_14") (pintype "bidirectional"))
    )
    (net (code "12") (name "/RES_7") (class "Default")
      (node (ref "D10") (pin "A") (pinfunction "A_A") (pintype "passive"))
      (node (ref "Q4") (pin "3") (pinfunction "G2_3") (pintype "passive"))
      (node (ref "U3") (pin "13") (pinfunction "P2.0/PM_TD0.2_13") (pintype "bidirectional"))
    )
    (net (code "13") (name "/RES_8") (class "Default")
      (node (ref "D11") (pin "A") (pinfunction "A_A") (pintype "passive"))
      (node (ref "Q5") (pin "1") (pinfunction "G1_1") (pintype "passive"))
      (node (ref "U3") (pin "12") (pinfunction "P1.7/PM_TD0.1_12") (pintype "bidirectional"))
    )
    (net (code "14") (name "/RES_9") (class "Default")
      (node (ref "D12") (pin "A") (pinfunction "A_A") (pintype "passive"))
      (node (ref "Q5") (pin "3") (pinfunction "G2_3") (pintype "passive"))
      (node (ref "U3") (pin "11") (pinfunction "P1.6/PM_TD0.0_11") (pintype "bidirectional"))
    )
    (net (code "15") (name "/SCL") (class "Default")
      (node (ref "R1") (pin "1") (pinfunction "1_1") (pintype "passive"))
      (node (ref "U1") (pin "5") (pinfunction "SCL_5") (pintype "passive"))
      (node (ref "U3") (pin "6") (pinfunction "P1.5/PM_UCB0SOMI/PM_UCB0SCL/A5/CB5_6") (pintype "bidirectional"))
    )
    (net (code "16") (name "/SDA") (class "Default")
      (node (ref "R2") (pin "1") (pinfunction "1_1") (pintype "passive"))
      (node (ref "U1") (pin "4") (pinfunction "SDA_4") (pintype "passive"))
      (node (ref "U3") (pin "5") (pinfunction "P1.4/PM_UCB0SIMO/PM_UCB0SDA/A4/CB4_5") (pintype "bidirectional"))
    )
    (net (code "17") (name "/TEST") (class "Default")
      (node (ref "U2") (pin "19") (pinfunction "RTS#_19") (pintype "passive"))
      (node (ref "U3") (pin "32") (pinfunction "TEST/SBWTCK_32") (pintype "input"))
    )
    (net (code "18") (name "/USB_RXDI") (class "Default")
      (node (ref "U2") (pin "1") (pinfunction "RXD_1") (pintype "passive"))
      (node (ref "U3") (pin "2") (pinfunction "P1.1/PM_UCA0TXD/PM_UCA0SIMO/A1/CB1_2") (pintype "bidirectional"))
      (node (ref "U3") (pin "36") (pinfunction "P3.7/PM_TA0.0/A6/CB10_36") (pintype "bidirectional"))
    )
    (net (code "19") (name "/USB_TXDO") (class "Default")
      (node (ref "U2") (pin "17") (pinfunction "TXD_17") (pintype "passive"))
      (node (ref "U3") (pin "3") (pinfunction "P1.2/PM_UCA0RXD/PM_UCA0SOMI/A2/CB2_3") (pintype "bidirectional"))
      (node (ref "U3") (pin "35") (pinfunction "P3.6/PM_TA0.1/A7/VEREF-/CB11_35") (pintype "bidirectional"))
    )
    (net (code "20") (name "/VCORE") (class "Default")
      (node (ref "C13") (pin "2") (pintype "passive"))
      (node (ref "U3") (pin "25") (pinfunction "VCORE_25") (pintype "passive"))
    )
    (net (code "21") (name "5V") (class "Default")
      (node (ref "C1") (pin "2") (pintype "passive"))
      (node (ref "C2") (pin "1") (pintype "power_in"))
      (node (ref "C3") (pin "2") (pintype "power_in"))
      (node (ref "L1") (pin "2") (pinfunction "2_2") (pintype "passive"))
      (node (ref "R7") (pin "2") (pinfunction "2_2") (pintype "passive"))
      (node (ref "U2") (pin "12") (pinfunction "VCC_12") (pintype "passive"))
    )
    (net (code "22") (name "GND") (class "Default")
      (node (ref "C1") (pin "1") (pintype "passive"))
      (node (ref "C10") (pin "2") (pintype "power_in"))
      (node (ref "C11") (pin "2") (pintype "passive"))
      (node (ref "C12") (pin "1") (pintype "passive"))
      (node (ref "C13") (pin "1") (pintype "passive"))
      (node (ref "C14") (pin "2") (pintype "power_in"))
      (node (ref "C15") (pin "2") (pintype "passive"))
      (node (ref "C16") (pin "2") (pintype "power_in"))
      (node (ref "C17") (pin "2") (pintype "passive"))
      (node (ref "C2") (pin "2") (pintype "power_in"))
      (node (ref "C3") (pin "1") (pintype "power_in"))
      (node (ref "C5") (pin "2") (pintype "power_in"))
      (node (ref "C6") (pin "2") (pintype "power_in"))
      (node (ref "C7") (pin "2") (pintype "power_in"))
      (node (ref "C8") (pin "2") (pintype "passive"))
      (node (ref "C9") (pin "2") (pintype "passive"))
      (node (ref "D1") (pin "2") (pinfunction "2_2") (pintype "passive"))
      (node (ref "D2") (pin "2") (pinfunction "2_2") (pintype "passive"))
      (node (ref "J1") (pin "10") (pinfunction "10_10") (pintype "passive"))
      (node (ref "J1") (pin "11") (pinfunction "11_11") (pintype "passive"))
      (node (ref "J1") (pin "5") (pinfunction "GND_5") (pintype "passive"))
      (node (ref "J1") (pin "6") (pinfunction "6_6") (pintype "passive"))
      (node (ref "J1") (pin "7") (pinfunction "7_7") (pintype "passive"))
      (node (ref "J1") (pin "8") (pinfunction "8_8") (pintype "passive"))
      (node (ref "J1") (pin "9") (pinfunction "9_9") (pintype "passive"))
      (node (ref "J2") (pin "10") (pinfunction "10_10") (pintype "passive"))
      (node (ref "J2") (pin "2") (pinfunction "2_2") (pintype "passive"))
      (node (ref "J2") (pin "4") (pinfunction "4_4") (pintype "passive"))
      (node (ref "J2") (pin "6") (pinfunction "6_6") (pintype "passive"))
      (node (ref "J2") (pin "8") (pinfunction "8_8") (pintype "passive"))
      (node (ref "Q1") (pin "2") (pinfunction "CS_2") (pintype "power_in"))
      (node (ref "Q2") (pin "2") (pinfunction "CS_2") (pintype "power_in"))
      (node (ref "Q3") (pin "2") (pinfunction "CS_2") (pintype "power_in"))
      (node (ref "Q4") (pin "2") (pinfunction "CS_2") (pintype "power_in"))
      (node (ref "Q5") (pin "2") (pinfunction "CS_2") (pintype "power_in"))
      (node (ref "R27") (pin "1") (pinfunction "1_1") (pintype "passive"))
      (node (ref "R28") (pin "1") (pinfunction "1_1") (pintype "passive"))
      (node (ref "R29") (pin "1") (pinfunction "1_1") (pintype "passive"))
      (node (ref "R30") (pin "1") (pinfunction "1_1") (pintype "passive"))
      (node (ref "R31") (pin "1") (pinfunction "1_1") (pintype "passive"))
      (node (ref "R32") (pin "1") (pinfunction "1_1") (pintype "passive"))
      (node (ref "R42") (pin "1") (pinfunction "1_1") (pintype "passive"))
      (node (ref "R43") (pin "1") (pinfunction "1_1") (pintype "passive"))
      (node (ref "R44") (pin "1") (pinfunction "1_1") (pintype "passive"))
      (node (ref "R48") (pin "1") (pinfunction "1_1") (pintype "passive"))
      (node (ref "S1") (pin "1") (pinfunction "1_1") (pintype "passive"))
      (node (ref "S1") (pin "2") (pinfunction "2_2") (pintype "passive"))
      (node (ref "U1") (pin "7") (pinfunction "GND_7") (pintype "passive"))
      (node (ref "U2") (pin "13") (pinfunction "GND_13") (pintype "passive"))
      (node (ref "U2") (pin "21") (pinfunction "GND_21") (pintype "passive"))
      (node (ref "U2") (pin "3") (pinfunction "GND_3") (pintype "passive"))
      (node (ref "U3") (pin "18") (pinfunction "DVSS_18") (pintype "power_in"))
      (node (ref "U3") (pin "26") (pinfunction "DVSS_26") (pintype "power_in"))
      (node (ref "U3") (pin "40") (pinfunction "AVSS_40") (pintype "power_in"))
      (node (ref "U3") (pin "41") (pinfunction "QFN_PAD_41") (pintype "power_in"))
      (node (ref "X1") (pin "2") (pinfunction "2_2") (pintype "passive"))
      (node (ref "X1") (pin "4") (pinfunction "4_4") (pintype "passive"))
    )
    (net (code "23") (name "Net-(D1-Pad1)") (class "Default")
      (node (ref "D1") (pin "1") (pinfunction "1_1") (pintype "passive"))
      (node (ref "R7") (pin "1") (pinfunction "1_1") (pintype "passive"))
    )
    (net (code "24") (name "Net-(D2-Pad1)") (class "Default")
      (node (ref "D2") (pin "1") (pinfunction "1_1") (pintype "passive"))
      (node (ref "R8") (pin "1") (pinfunction "1_1") (pintype "passive"))
    )
    (net (code "25") (name "Net-(D3-PadC)") (class "Default")
      (node (ref "D3") (pin "C") (pinfunction "C_C") (pintype "passive"))
      (node (ref "R27") (pin "2") (pinfunction "2_2") (pintype "passive"))
    )
    (net (code "26") (name "Net-(D4-PadC)") (class "Default")
      (node (ref "D4") (pin "C") (pinfunction "C_C") (pintype "passive"))
      (node (ref "R28") (pin "2") (pinfunction "2_2") (pintype "passive"))
    )
    (net (code "27") (name "Net-(D5-PadC)") (class "Default")
      (node (ref "D5") (pin "C") (pinfunction "C_C") (pintype "passive"))
      (node (ref "R29") (pin "2") (pinfunction "2_2") (pintype "passive"))
    )
    (net (code "28") (name "Net-(D6-PadC)") (class "Default")
      (node (ref "D6") (pin "C") (pinfunction "C_C") (pintype "passive"))
      (node (ref "R30") (pin "2") (pinfunction "2_2") (pintype "passive"))
    )
    (net (code "29") (name "Net-(D7-PadC)") (class "Default")
      (node (ref "D7") (pin "C") (pinfunction "C_C") (pintype "passive"))
      (node (ref "R31") (pin "2") (pinfunction "2_2") (pintype "passive"))
    )
    (net (code "30") (name "Net-(D8-PadC)") (class "Default")
      (node (ref "D8") (pin "C") (pinfunction "C_C") (pintype "passive"))
      (node (ref "R32") (pin "2") (pinfunction "2_2") (pintype "passive"))
    )
    (net (code "31") (name "Net-(D9-PadC)") (class "Default")
      (node (ref "D9") (pin "C") (pinfunction "C_C") (pintype "passive"))
      (node (ref "R42") (pin "2") (pinfunction "2_2") (pintype "passive"))
    )
    (net (code "32") (name "Net-(D10-PadC)") (class "Default")
      (node (ref "D10") (pin "C") (pinfunction "C_C") (pintype "passive"))
      (node (ref "R43") (pin "2") (pinfunction "2_2") (pintype "passive"))
    )
    (net (code "33") (name "Net-(D11-PadC)") (class "Default")
      (node (ref "D11") (pin "C") (pinfunction "C_C") (pintype "passive"))
      (node (ref "R44") (pin "2") (pinfunction "2_2") (pintype "passive"))
    )
    (net (code "34") (name "Net-(D12-PadC)") (class "Default")
      (node (ref "D12") (pin "C") (pinfunction "C_C") (pintype "passive"))
      (node (ref "R48") (pin "2") (pinfunction "2_2") (pintype "passive"))
    )
    (net (code "35") (name "Net-(J1-D+)") (class "Default")
      (node (ref "C9") (pin "1") (pintype "passive"))
      (node (ref "J1") (pin "3") (pinfunction "D+_3") (pintype "passive"))
      (node (ref "R6") (pin "1") (pinfunction "1_1") (pintype "passive"))
    )
    (net (code "36") (name "Net-(J1-D-)") (class "Default")
      (node (ref "C8") (pin "1") (pintype "passive"))
      (node (ref "J1") (pin "2") (pinfunction "D-_2") (pintype "passive"))
      (node (ref "R5") (pin "1") (pinfunction "1_1") (pintype "passive"))
    )
    (net (code "37") (name "Net-(J1-VCC)") (class "Default")
      (node (ref "C7") (pin "1") (pintype "power_in"))
      (node (ref "J1") (pin "1") (pinfunction "VCC_1") (pintype "passive"))
      (node (ref "L1") (pin "1") (pinfunction "1_1") (pintype "passive"))
    )
    (net (code "38") (name "Net-(Q1-D1)") (class "Default")
      (node (ref "Q1") (pin "5") (pinfunction "D1_5") (pintype "passive"))
      (node (ref "R15") (pin "1") (pinfunction "1_1") (pintype "passive"))
    )
    (net (code "39") (name "Net-(Q1-D2)") (class "Default")
      (node (ref "Q1") (pin "4") (pinfunction "D2_4") (pintype "power_in"))
      (node (ref "R16") (pin "1") (pinfunction "1_1") (pintype "passive"))
    )
    (net (code "40") (name "Net-(Q2-D1)") (class "Default")
      (node (ref "Q2") (pin "5") (pinfunction "D1_5") (pintype "passive"))
      (node (ref "R17") (pin "1") (pinfunction "1_1") (pintype "passive"))
    )
    (net (code "41") (name "Net-(Q2-D2)") (class "Default")
      (node (ref "Q2") (pin "4") (pinfunction "D2_4") (pintype "power_in"))
      (node (ref "R18") (pin "1") (pinfunction "1_1") (pintype "passive"))
    )
    (net (code "42") (name "Net-(Q3-D1)") (class "Default")
      (node (ref "Q3") (pin "5") (pinfunction "D1_5") (pintype "passive"))
      (node (ref "R19") (pin "1") (pinfunction "1_1") (pintype "passive"))
    )
    (net (code "43") (name "Net-(Q3-D2)") (class "Default")
      (node (ref "Q3") (pin "4") (pinfunction "D2_4") (pintype "power_in"))
      (node (ref "R20") (pin "1") (pinfunction "1_1") (pintype "passive"))
    )
    (net (code "44") (name "Net-(Q4-D1)") (class "Default")
      (node (ref "Q4") (pin "5") (pinfunction "D1_5") (pintype "passive"))
      (node (ref "R25") (pin "1") (pinfunction "1_1") (pintype "passive"))
    )
    (net (code "45") (name "Net-(Q4-D2)") (class "Default")
      (node (ref "Q4") (pin "4") (pinfunction "D2_4") (pintype "power_in"))
      (node (ref "R26") (pin "1") (pinfunction "1_1") (pintype "passive"))
    )
    (net (code "46") (name "Net-(Q5-D1)") (class "Default")
      (node (ref "Q5") (pin "5") (pinfunction "D1_5") (pintype "passive"))
      (node (ref "R33") (pin "1") (pinfunction "1_1") (pintype "passive"))
    )
    (net (code "47") (name "Net-(Q5-D2)") (class "Default")
      (node (ref "Q5") (pin "4") (pinfunction "D2_4") (pintype "power_in"))
      (node (ref "R34") (pin "1") (pinfunction "1_1") (pintype "passive"))
    )
    (net (code "48") (name "Net-(R10-Pad1)") (class "Default")
      (node (ref "R10") (pin "1") (pinfunction "1_1") (pintype "passive"))
      (node (ref "R16") (pin "2") (pinfunction "2_2") (pintype "passive"))
    )
    (net (code "49") (name "Net-(R11-Pad1)") (class "Default")
      (node (ref "R11") (pin "1") (pinfunction "1_1") (pintype "passive"))
      (node (ref "R17") (pin "2") (pinfunction "2_2") (pintype "passive"))
    )
    (net (code "50") (name "Net-(R12-Pad1)") (class "Default")
      (node (ref "R12") (pin "1") (pinfunction "1_1") (pintype "passive"))
      (node (ref "R18") (pin "2") (pinfunction "2_2") (pintype "passive"))
    )
    (net (code "51") (name "Net-(R13-Pad1)") (class "Default")
      (node (ref "R13") (pin "1") (pinfunction "1_1") (pintype "passive"))
      (node (ref "R19") (pin "2") (pinfunction "2_2") (pintype "passive"))
    )
    (net (code "52") (name "Net-(R14-Pad1)") (class "Default")
      (node (ref "R14") (pin "1") (pinfunction "1_1") (pintype "passive"))
      (node (ref "R20") (pin "2") (pinfunction "2_2") (pintype "passive"))
    )
    (net (code "53") (name "Net-(R15-Pad2)") (class "Default")
      (node (ref "R15") (pin "2") (pinfunction "2_2") (pintype "passive"))
      (node (ref "R9") (pin "1") (pinfunction "1_1") (pintype "passive"))
    )
    (net (code "54") (name "Net-(R21-Pad1)") (class "Default")
      (node (ref "R21") (pin "1") (pinfunction "1_1") (pintype "passive"))
      (node (ref "R25") (pin "2") (pinfunction "2_2") (pintype "passive"))
    )
    (net (code "55") (name "Net-(R22-Pad1)") (class "Default")
      (node (ref "R22") (pin "1") (pinfunction "1_1") (pintype "passive"))
      (node (ref "R26") (pin "2") (pinfunction "2_2") (pintype "passive"))
    )
    (net (code "56") (name "Net-(R23-Pad1)") (class "Default")
      (node (ref "R23") (pin "1") (pinfunction "1_1") (pintype "passive"))
      (node (ref "R33") (pin "2") (pinfunction "2_2") (pintype "passive"))
    )
    (net (code "57") (name "Net-(R24-Pad1)") (class "Default")
      (node (ref "R24") (pin "1") (pinfunction "1_1") (pintype "passive"))
      (node (ref "R34") (pin "2") (pinfunction "2_2") (pintype "passive"))
    )
    (net (code "58") (name "Net-(U2-USBDM)") (class "Default")
      (node (ref "R5") (pin "2") (pinfunction "2_2") (pintype "passive"))
      (node (ref "U2") (pin "9") (pinfunction "USBDM_9") (pintype "passive"))
    )
    (net (code "59") (name "Net-(U2-USBDP)") (class "Default")
      (node (ref "R6") (pin "2") (pinfunction "2_2") (pintype "passive"))
      (node (ref "U2") (pin "8") (pinfunction "USBDP_8") (pintype "passive"))
    )
    (net (code "60") (name "Net-(U3-PJ.4{slash}XOUT)") (class "Default")
      (node (ref "C11") (pin "1") (pintype "passive"))
      (node (ref "U3") (pin "38") (pinfunction "PJ.4/XOUT_38") (pintype "bidirectional"))
      (node (ref "X1") (pin "1") (pinfunction "1_1") (pintype "passive"))
    )
    (net (code "61") (name "Net-(U3-PJ.5{slash}XIN)") (class "Default")
      (node (ref "C12") (pin "2") (pintype "passive"))
      (node (ref "U3") (pin "39") (pinfunction "PJ.5/XIN_39") (pintype "bidirectional"))
      (node (ref "X1") (pin "3") (pinfunction "3_3") (pintype "passive"))
    )
    (net (code "62") (name "VDD_3V3") (class "Default")
      (node (ref "C10") (pin "1") (pintype "power_in"))
      (node (ref "C14") (pin "1") (pintype "power_in"))
      (node (ref "C15") (pin "1") (pintype "passive"))
      (node (ref "C17") (pin "1") (pintype "passive"))
      (node (ref "C5") (pin "1") (pintype "power_in"))
      (node (ref "L2") (pin "2") (pinfunction "2_2") (pintype "passive"))
      (node (ref "R1") (pin "2") (pinfunction "2_2") (pintype "passive"))
      (node (ref "R2") (pin "2") (pinfunction "2_2") (pintype "passive"))
      (node (ref "R4") (pin "2") (pinfunction "2_2") (pintype "passive"))
      (node (ref "R8") (pin "2") (pinfunction "2_2") (pintype "passive"))
      (node (ref "U1") (pin "1") (pinfunction "A1_1") (pintype "passive"))
      (node (ref "U1") (pin "2") (pinfunction "A0_2") (pintype "passive"))
      (node (ref "U1") (pin "6") (pinfunction "VS+_6") (pintype "passive"))
      (node (ref "U2") (pin "10") (pinfunction "3V3OUT_10") (pintype "passive"))
      (node (ref "U2") (pin "11") (pinfunction "RESET#_11") (pintype "passive"))
      (node (ref "U2") (pin "20") (pinfunction "VCCIO_20") (pintype "passive"))
      (node (ref "U3") (pin "17") (pinfunction "DVIO_17") (pintype "power_in"))
      (node (ref "U3") (pin "27") (pinfunction "DVCC_27") (pintype "power_in"))
    )
    (net (code "63") (name "unconnected-(J1-NC-Pad4)") (class "Default")
      (node (ref "J1") (pin "4") (pinfunction "NC_4") (pintype "passive"))
    )
    (net (code "64") (name "unconnected-(U1-Alert-Pad3)") (class "Default")
      (node (ref "U1") (pin "3") (pinfunction "Alert_3") (pintype "passive"))
    )
    (net (code "65") (name "unconnected-(U2-CBUS0-Pad15)") (class "Default")
      (node (ref "U2") (pin "15") (pinfunction "CBUS0_15") (pintype "passive"))
    )
    (net (code "66") (name "unconnected-(U2-CBUS1-Pad14)") (class "Default")
      (node (ref "U2") (pin "14") (pinfunction "CBUS1_14") (pintype "passive"))
    )
    (net (code "67") (name "unconnected-(U2-CBUS2-Pad7)") (class "Default")
      (node (ref "U2") (pin "7") (pinfunction "CBUS2_7") (pintype "passive"))
    )
    (net (code "68") (name "unconnected-(U2-CBUS3-Pad16)") (class "Default")
      (node (ref "U2") (pin "16") (pinfunction "CBUS3_16") (pintype "passive"))
    )
    (net (code "69") (name "unconnected-(U2-CTS#-Pad6)") (class "Default")
      (node (ref "U2") (pin "6") (pinfunction "CTS#_6") (pintype "passive"))
    )
    (net (code "70") (name "unconnected-(U2-DCD#-Pad5)") (class "Default")
      (node (ref "U2") (pin "5") (pinfunction "DCD#_5") (pintype "passive"))
    )
    (net (code "71") (name "unconnected-(U2-DSR#-Pad4)") (class "Default")
      (node (ref "U2") (pin "4") (pinfunction "DSR#_4") (pintype "passive"))
    )
    (net (code "72") (name "unconnected-(U2-RI#-Pad2)") (class "Default")
      (node (ref "U2") (pin "2") (pinfunction "RI#_2") (pintype "passive"))
    )
    (net (code "73") (name "unconnected-(U3-P1.0{slash}PM_UCA0CLK{slash}PM_UCB0STE{slash}A0{slash}CB0-Pad1)") (class "Default")
      (node (ref "U3") (pin "1") (pinfunction "P1.0/PM_UCA0CLK/PM_UCB0STE/A0/CB0_1") (pintype "bidirectional"))
    )
    (net (code "74") (name "unconnected-(U3-P1.3{slash}PM_UCB0CLK{slash}PM_UCA0STE{slash}A3{slash}CB3-Pad4)") (class "Default")
      (node (ref "U3") (pin "4") (pinfunction "P1.3/PM_UCB0CLK/PM_UCA0STE/A3/CB3_4") (pintype "bidirectional"))
    )
    (net (code "75") (name "unconnected-(U3-P3.0{slash}TEC1FLT2{slash}PM_TD1.1-Pad23)") (class "Default")
      (node (ref "U3") (pin "23") (pinfunction "P3.0/TEC1FLT2/PM_TD1.1_23") (pintype "bidirectional"))
    )
    (net (code "76") (name "unconnected-(U3-P3.1{slash}PM_TEC1FLT0{slash}PM_TD1.2-Pad24)") (class "Default")
      (node (ref "U3") (pin "24") (pinfunction "P3.1/PM_TEC1FLT0/PM_TD1.2_24") (pintype "bidirectional"))
    )
    (net (code "77") (name "unconnected-(U3-P3.2{slash}PM_TD0.0{slash}PM_SMCLK{slash}CB14-Pad29)") (class "Default")
      (node (ref "U3") (pin "29") (pinfunction "P3.2/PM_TD0.0/PM_SMCLK/CB14_29") (pintype "bidirectional"))
    )
    (net (code "78") (name "unconnected-(U3-P3.3{slash}PM_TA0CLK{slash}PM_CBOUT{slash}CB13-Pad30)") (class "Default")
      (node (ref "U3") (pin "30") (pinfunction "P3.3/PM_TA0CLK/PM_CBOUT/CB13_30") (pintype "bidirectional"))
    )
    (net (code "79") (name "unconnected-(U3-P3.4{slash}PM_TD0CLK{slash}PM_MCLK-Pad31)") (class "Default")
      (node (ref "U3") (pin "31") (pinfunction "P3.4/PM_TD0CLK/PM_MCLK_31") (pintype "bidirectional"))
    )
    (net (code "80") (name "unconnected-(U3-P3.5{slash}PM_TA0.2{slash}A8{slash}VEREF+{slash}CB12-Pad34)") (class "Default")
      (node (ref "U3") (pin "34") (pinfunction "P3.5/PM_TA0.2/A8/VEREF+/CB12_34") (pintype "bidirectional"))
    )
    (net (code "81") (name "unconnected-(U3-PJ.0{slash}SMCLK{slash}TDO{slash}CB6-Pad7)") (class "Default")
      (node (ref "U3") (pin "7") (pinfunction "PJ.0/SMCLK/TDO/CB6_7") (pintype "bidirectional"))
    )
    (net (code "82") (name "unconnected-(U3-PJ.1{slash}MCLK{slash}TDI{slash}TCLK{slash}CB7-Pad8)") (class "Default")
      (node (ref "U3") (pin "8") (pinfunction "PJ.1/MCLK/TDI/TCLK/CB7_8") (pintype "bidirectional"))
    )
    (net (code "83") (name "unconnected-(U3-PJ.2{slash}ADC10CLK{slash}TMS{slash}CB8-Pad9)") (class "Default")
      (node (ref "U3") (pin "9") (pinfunction "PJ.2/ADC10CLK/TMS/CB8_9") (pintype "bidirectional"))
    )
    (net (code "84") (name "unconnected-(U3-PJ.3{slash}ACLK{slash}TCK{slash}CB9-Pad10)") (class "Default")
      (node (ref "U3") (pin "10") (pinfunction "PJ.3/ACLK/TCK/CB9_10") (pintype "bidirectional"))
    )
    (net (code "85") (name "unconnected-(U3-PJ.6{slash}TD1CLK{slash}TD0.1{slash}CB15-Pad28)") (class "Default")
      (node (ref "U3") (pin "28") (pinfunction "PJ.6/TD1CLK/TD0.1/CB15_28") (pintype "bidirectional"))
    )
  )
)
